# woodenHaptics_v_0_1.net
KiCad netlist of a schematic drawn in EAGLE
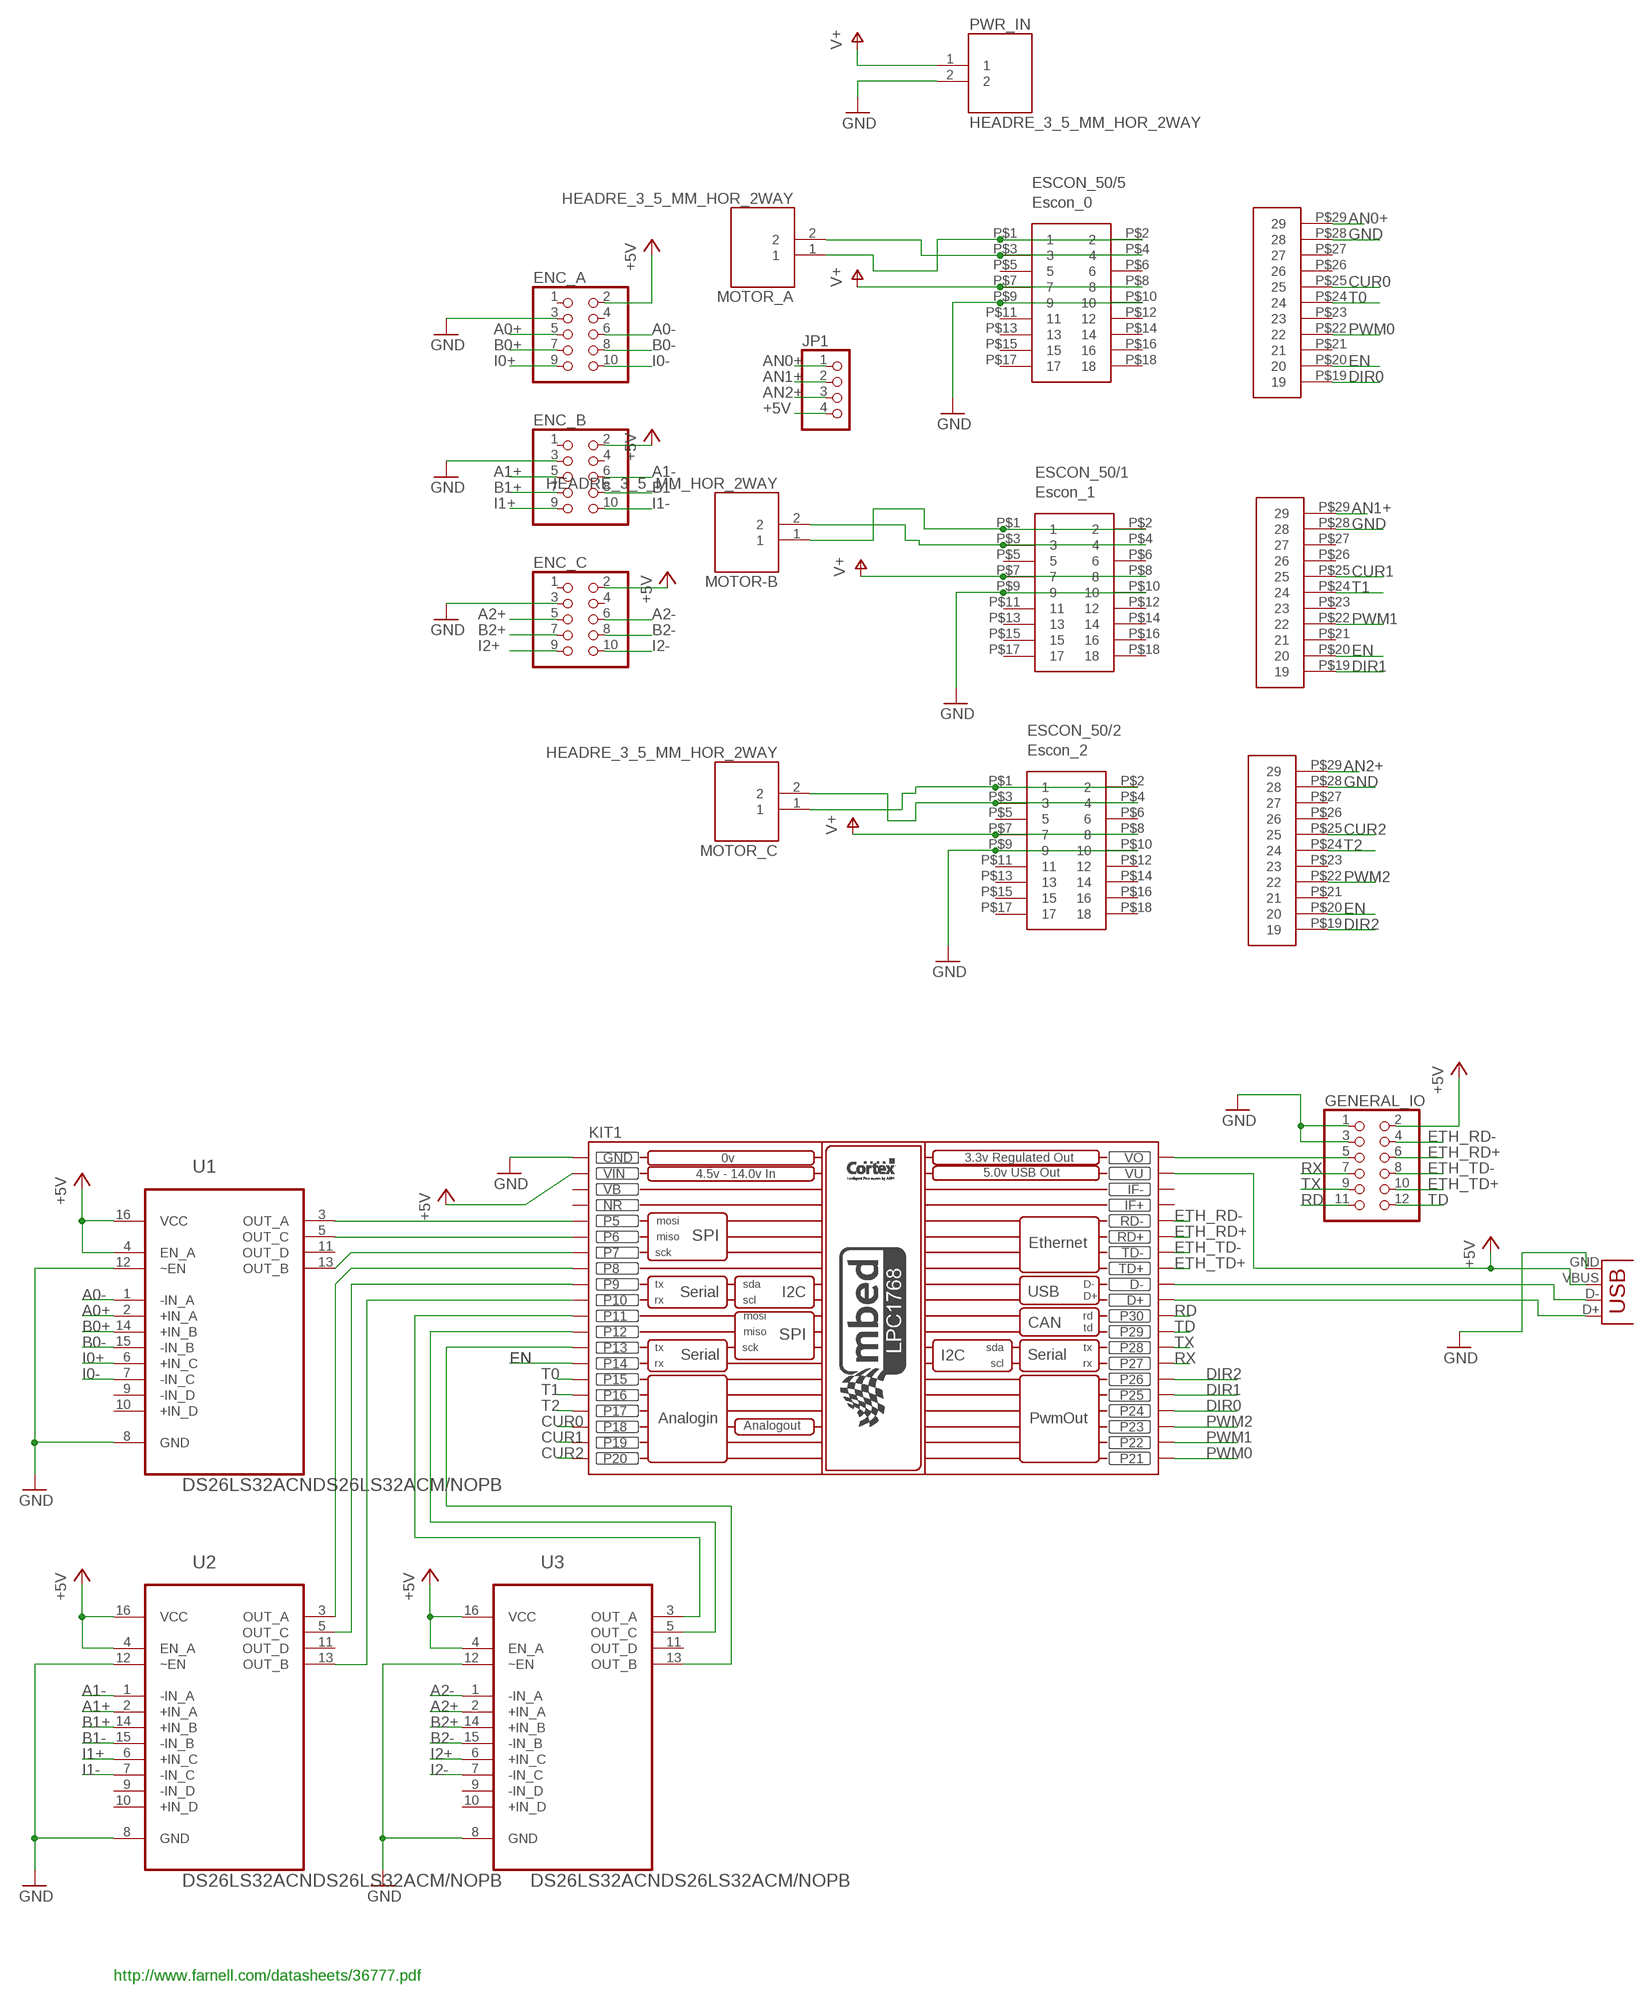
[diagram p0: schematic, sheet 1]

(export (version "E")
  (design (tool "Eeschema 10.0.6"))
  (components
    (comp (ref "ENC_A")
      (value "PINHD-2X5")
      (footprint "eagle-import:2X05")
      (libsource (lib "eagle-import") (part "PINHD-2X5"))
    )
    (comp (ref "ENC_B")
      (value "PINHD-2X5")
      (footprint "eagle-import:2X05")
      (libsource (lib "eagle-import") (part "PINHD-2X5"))
    )
    (comp (ref "ENC_C")
      (value "PINHD-2X5")
      (footprint "eagle-import:2X05")
      (libsource (lib "eagle-import") (part "PINHD-2X5"))
    )
    (comp (ref "ESCON_50/1")
      (value "Escon_1")
      (footprint "eagle-import:MODULE")
      (libsource (lib "eagle-import") (part "ESCON_MODULE_50/5"))
    )
    (comp (ref "ESCON_50/2")
      (value "Escon_2")
      (footprint "eagle-import:MODULE")
      (libsource (lib "eagle-import") (part "ESCON_MODULE_50/5"))
    )
    (comp (ref "ESCON_50/5")
      (value "Escon_0")
      (footprint "eagle-import:MODULE")
      (libsource (lib "eagle-import") (part "ESCON_MODULE_50/5"))
    )
    (comp (ref "GENERAL_IO")
      (value "PINHD-2X6")
      (footprint "eagle-import:2X06")
      (libsource (lib "eagle-import") (part "PINHD-2X6"))
    )
    (comp (ref "JP1")
      (value "PINHD-1X4")
      (footprint "eagle-import:1X04")
      (libsource (lib "eagle-import") (part "PINHD-1X4"))
    )
    (comp (ref "KIT1")
      (value "MBED_NXP_LPC1768")
      (footprint "eagle-import:MBED-KIT")
      (libsource (lib "eagle-import") (part "MBED_NXP_LPC1768"))
    )
    (comp (ref "MOTOR-B")
      (value "HEADRE_3_5_MM_HOR_2WAY")
      (footprint "eagle-import:HEADER_3_5MM_HOR_2WAY")
      (libsource (lib "eagle-import") (part "HEADRE_3_5_MM_HOR_2WAY"))
    )
    (comp (ref "MOTOR_A")
      (value "HEADRE_3_5_MM_HOR_2WAY")
      (footprint "eagle-import:HEADER_3_5MM_HOR_2WAY")
      (libsource (lib "eagle-import") (part "HEADRE_3_5_MM_HOR_2WAY"))
    )
    (comp (ref "MOTOR_C")
      (value "HEADRE_3_5_MM_HOR_2WAY")
      (footprint "eagle-import:HEADER_3_5MM_HOR_2WAY")
      (libsource (lib "eagle-import") (part "HEADRE_3_5_MM_HOR_2WAY"))
    )
    (comp (ref "PWR_IN")
      (value "HEADRE_3_5_MM_HOR_2WAY")
      (footprint "eagle-import:HEADER_3_5MM_HOR_2WAY")
      (libsource (lib "eagle-import") (part "HEADRE_3_5_MM_HOR_2WAY"))
    )
    (comp (ref "U1")
      (value "DS26LS32ACNDS26LS32ACM/NOPB")
      (footprint "eagle-import:M16")
      (libsource (lib "eagle-import") (part "DS26LS32ACNDS26LS32ACM/NOPB"))
    )
    (comp (ref "U2")
      (value "DS26LS32ACNDS26LS32ACM/NOPB")
      (footprint "eagle-import:M16")
      (libsource (lib "eagle-import") (part "DS26LS32ACNDS26LS32ACM/NOPB"))
    )
    (comp (ref "U3")
      (value "DS26LS32ACNDS26LS32ACM/NOPB")
      (footprint "eagle-import:M16")
      (libsource (lib "eagle-import") (part "DS26LS32ACNDS26LS32ACM/NOPB"))
    )
    (comp (ref "X2")
      (value "Micro USB")
      (footprint "eagle-import:USB-MICROB")
      (libsource (lib "eagle-import") (part "USB-MICROB"))
    )
  )
  (nets
    (net (code "1") (name "+5V") (class "Default")
      (node (ref "ENC_A") (pin "2") (pinfunction "2_2") (pintype "passive"))
      (node (ref "ENC_B") (pin "2") (pinfunction "2_2") (pintype "passive"))
      (node (ref "ENC_C") (pin "2") (pinfunction "2_2") (pintype "passive"))
      (node (ref "GENERAL_IO") (pin "2") (pinfunction "2_2") (pintype "passive"))
      (node (ref "JP1") (pin "4") (pinfunction "4_4") (pintype "passive"))
      (node (ref "KIT1") (pin "VIN") (pinfunction "VIN_VIN") (pintype "power_in"))
      (node (ref "KIT1") (pin "VU") (pinfunction "VU_VU") (pintype "power_in"))
      (node (ref "U1") (pin "16") (pinfunction "VCC_16") (pintype "power_in"))
      (node (ref "U1") (pin "4") (pinfunction "EN_A_4") (pintype "input"))
      (node (ref "U2") (pin "16") (pinfunction "VCC_16") (pintype "power_in"))
      (node (ref "U2") (pin "4") (pinfunction "EN_A_4") (pintype "input"))
      (node (ref "U3") (pin "16") (pinfunction "VCC_16") (pintype "power_in"))
      (node (ref "U3") (pin "4") (pinfunction "EN_A_4") (pintype "input"))
      (node (ref "X2") (pin "VBUS") (pinfunction "VBUS_VBUS") (pintype "bidirectional"))
    )
    (net (code "2") (name "/A0+") (class "Default")
      (node (ref "ENC_A") (pin "5") (pinfunction "5_5") (pintype "passive"))
      (node (ref "U1") (pin "2") (pinfunction "+IN_A_2") (pintype "input"))
    )
    (net (code "3") (name "/A0-") (class "Default")
      (node (ref "ENC_A") (pin "6") (pinfunction "6_6") (pintype "passive"))
      (node (ref "U1") (pin "1") (pinfunction "-IN_A_1") (pintype "input"))
    )
    (net (code "4") (name "/A1+") (class "Default")
      (node (ref "ENC_B") (pin "5") (pinfunction "5_5") (pintype "passive"))
      (node (ref "U2") (pin "2") (pinfunction "+IN_A_2") (pintype "input"))
    )
    (net (code "5") (name "/A1-") (class "Default")
      (node (ref "ENC_B") (pin "6") (pinfunction "6_6") (pintype "passive"))
      (node (ref "U2") (pin "1") (pinfunction "-IN_A_1") (pintype "input"))
    )
    (net (code "6") (name "/A2+") (class "Default")
      (node (ref "ENC_C") (pin "5") (pinfunction "5_5") (pintype "passive"))
      (node (ref "U3") (pin "2") (pinfunction "+IN_A_2") (pintype "input"))
    )
    (net (code "7") (name "/A2-") (class "Default")
      (node (ref "ENC_C") (pin "6") (pinfunction "6_6") (pintype "passive"))
      (node (ref "U3") (pin "1") (pinfunction "-IN_A_1") (pintype "input"))
    )
    (net (code "8") (name "/AN0+") (class "Default")
      (node (ref "ESCON_50/5") (pin "P$29") (pinfunction "29_P$29") (pintype "bidirectional"))
      (node (ref "JP1") (pin "1") (pinfunction "1_1") (pintype "passive"))
    )
    (net (code "9") (name "/AN1+") (class "Default")
      (node (ref "ESCON_50/1") (pin "P$29") (pinfunction "29_P$29") (pintype "bidirectional"))
      (node (ref "JP1") (pin "2") (pinfunction "2_2") (pintype "passive"))
    )
    (net (code "10") (name "/AN2+") (class "Default")
      (node (ref "ESCON_50/2") (pin "P$29") (pinfunction "29_P$29") (pintype "bidirectional"))
      (node (ref "JP1") (pin "3") (pinfunction "3_3") (pintype "passive"))
    )
    (net (code "11") (name "/B0+") (class "Default")
      (node (ref "ENC_A") (pin "7") (pinfunction "7_7") (pintype "passive"))
      (node (ref "U1") (pin "14") (pinfunction "+IN_B_14") (pintype "input"))
    )
    (net (code "12") (name "/B0-") (class "Default")
      (node (ref "ENC_A") (pin "8") (pinfunction "8_8") (pintype "passive"))
      (node (ref "U1") (pin "15") (pinfunction "-IN_B_15") (pintype "input"))
    )
    (net (code "13") (name "/B1+") (class "Default")
      (node (ref "ENC_B") (pin "7") (pinfunction "7_7") (pintype "passive"))
      (node (ref "U2") (pin "14") (pinfunction "+IN_B_14") (pintype "input"))
    )
    (net (code "14") (name "/B1-") (class "Default")
      (node (ref "ENC_B") (pin "8") (pinfunction "8_8") (pintype "passive"))
      (node (ref "U2") (pin "15") (pinfunction "-IN_B_15") (pintype "input"))
    )
    (net (code "15") (name "/B2+") (class "Default")
      (node (ref "ENC_C") (pin "7") (pinfunction "7_7") (pintype "passive"))
      (node (ref "U3") (pin "14") (pinfunction "+IN_B_14") (pintype "input"))
    )
    (net (code "16") (name "/B2-") (class "Default")
      (node (ref "ENC_C") (pin "8") (pinfunction "8_8") (pintype "passive"))
      (node (ref "U3") (pin "15") (pinfunction "-IN_B_15") (pintype "input"))
    )
    (net (code "17") (name "/CUR0") (class "Default")
      (node (ref "ESCON_50/5") (pin "P$25") (pinfunction "25_P$25") (pintype "bidirectional"))
      (node (ref "KIT1") (pin "P$18") (pinfunction "P18_P$18") (pintype "bidirectional"))
    )
    (net (code "18") (name "/CUR1") (class "Default")
      (node (ref "ESCON_50/1") (pin "P$25") (pinfunction "25_P$25") (pintype "bidirectional"))
      (node (ref "KIT1") (pin "P$19") (pinfunction "P19_P$19") (pintype "bidirectional"))
    )
    (net (code "19") (name "/CUR2") (class "Default")
      (node (ref "ESCON_50/2") (pin "P$25") (pinfunction "25_P$25") (pintype "bidirectional"))
      (node (ref "KIT1") (pin "P$20") (pinfunction "P20_P$20") (pintype "bidirectional"))
    )
    (net (code "20") (name "/DIR0") (class "Default")
      (node (ref "ESCON_50/5") (pin "P$19") (pinfunction "19_P$19") (pintype "bidirectional"))
      (node (ref "KIT1") (pin "P$24") (pinfunction "P24_P$24") (pintype "bidirectional"))
    )
    (net (code "21") (name "/DIR1") (class "Default")
      (node (ref "ESCON_50/1") (pin "P$19") (pinfunction "19_P$19") (pintype "bidirectional"))
      (node (ref "KIT1") (pin "P$25") (pinfunction "P25_P$25") (pintype "bidirectional"))
    )
    (net (code "22") (name "/DIR2") (class "Default")
      (node (ref "ESCON_50/2") (pin "P$19") (pinfunction "19_P$19") (pintype "bidirectional"))
      (node (ref "KIT1") (pin "P$26") (pinfunction "P26_P$26") (pintype "bidirectional"))
    )
    (net (code "23") (name "/EN") (class "Default")
      (node (ref "ESCON_50/1") (pin "P$20") (pinfunction "20_P$20") (pintype "bidirectional"))
      (node (ref "ESCON_50/2") (pin "P$20") (pinfunction "20_P$20") (pintype "bidirectional"))
      (node (ref "ESCON_50/5") (pin "P$20") (pinfunction "20_P$20") (pintype "bidirectional"))
      (node (ref "KIT1") (pin "P$14") (pinfunction "P14_P$14") (pintype "bidirectional"))
    )
    (net (code "24") (name "/ETH_RD+") (class "Default")
      (node (ref "GENERAL_IO") (pin "6") (pinfunction "6_6") (pintype "passive"))
      (node (ref "KIT1") (pin "RD+") (pinfunction "RD+_RD+") (pintype "bidirectional"))
    )
    (net (code "25") (name "/ETH_RD-") (class "Default")
      (node (ref "GENERAL_IO") (pin "4") (pinfunction "4_4") (pintype "passive"))
      (node (ref "KIT1") (pin "RD-") (pinfunction "RD-_RD-") (pintype "bidirectional"))
    )
    (net (code "26") (name "/ETH_TD+") (class "Default")
      (node (ref "GENERAL_IO") (pin "10") (pinfunction "10_10") (pintype "passive"))
      (node (ref "KIT1") (pin "TD+") (pinfunction "TD+_TD+") (pintype "bidirectional"))
    )
    (net (code "27") (name "/ETH_TD-") (class "Default")
      (node (ref "GENERAL_IO") (pin "8") (pinfunction "8_8") (pintype "passive"))
      (node (ref "KIT1") (pin "TD-") (pinfunction "TD-_TD-") (pintype "bidirectional"))
    )
    (net (code "28") (name "/I0+") (class "Default")
      (node (ref "ENC_A") (pin "9") (pinfunction "9_9") (pintype "passive"))
      (node (ref "U1") (pin "6") (pinfunction "+IN_C_6") (pintype "input"))
    )
    (net (code "29") (name "/I0-") (class "Default")
      (node (ref "ENC_A") (pin "10") (pinfunction "10_10") (pintype "passive"))
      (node (ref "U1") (pin "7") (pinfunction "-IN_C_7") (pintype "input"))
    )
    (net (code "30") (name "/I1+") (class "Default")
      (node (ref "ENC_B") (pin "9") (pinfunction "9_9") (pintype "passive"))
      (node (ref "U2") (pin "6") (pinfunction "+IN_C_6") (pintype "input"))
    )
    (net (code "31") (name "/I1-") (class "Default")
      (node (ref "ENC_B") (pin "10") (pinfunction "10_10") (pintype "passive"))
      (node (ref "U2") (pin "7") (pinfunction "-IN_C_7") (pintype "input"))
    )
    (net (code "32") (name "/I2+") (class "Default")
      (node (ref "ENC_C") (pin "9") (pinfunction "9_9") (pintype "passive"))
      (node (ref "U3") (pin "6") (pinfunction "+IN_C_6") (pintype "input"))
    )
    (net (code "33") (name "/I2-") (class "Default")
      (node (ref "ENC_C") (pin "10") (pinfunction "10_10") (pintype "passive"))
      (node (ref "U3") (pin "7") (pinfunction "-IN_C_7") (pintype "input"))
    )
    (net (code "34") (name "/NR") (class "Default")
      (node (ref "KIT1") (pin "NR") (pinfunction "NR_NR") (pintype "power_in"))
    )
    (net (code "35") (name "/PWM0") (class "Default")
      (node (ref "ESCON_50/5") (pin "P$22") (pinfunction "22_P$22") (pintype "bidirectional"))
      (node (ref "KIT1") (pin "P$21") (pinfunction "P21_P$21") (pintype "bidirectional"))
    )
    (net (code "36") (name "/PWM1") (class "Default")
      (node (ref "ESCON_50/1") (pin "P$22") (pinfunction "22_P$22") (pintype "bidirectional"))
      (node (ref "KIT1") (pin "P$22") (pinfunction "P22_P$22") (pintype "bidirectional"))
    )
    (net (code "37") (name "/PWM2") (class "Default")
      (node (ref "ESCON_50/2") (pin "P$22") (pinfunction "22_P$22") (pintype "bidirectional"))
      (node (ref "KIT1") (pin "P$23") (pinfunction "P23_P$23") (pintype "bidirectional"))
    )
    (net (code "38") (name "/RD") (class "Default")
      (node (ref "GENERAL_IO") (pin "11") (pinfunction "11_11") (pintype "passive"))
      (node (ref "KIT1") (pin "P$30") (pinfunction "P30_P$30") (pintype "bidirectional"))
    )
    (net (code "39") (name "/RX") (class "Default")
      (node (ref "GENERAL_IO") (pin "7") (pinfunction "7_7") (pintype "passive"))
      (node (ref "KIT1") (pin "P$27") (pinfunction "P27_P$27") (pintype "bidirectional"))
    )
    (net (code "40") (name "/T0") (class "Default")
      (node (ref "ESCON_50/5") (pin "P$24") (pinfunction "24_P$24") (pintype "bidirectional"))
      (node (ref "KIT1") (pin "P$15") (pinfunction "P15_P$15") (pintype "bidirectional"))
    )
    (net (code "41") (name "/T1") (class "Default")
      (node (ref "ESCON_50/1") (pin "P$24") (pinfunction "24_P$24") (pintype "bidirectional"))
      (node (ref "KIT1") (pin "P$16") (pinfunction "P16_P$16") (pintype "bidirectional"))
    )
    (net (code "42") (name "/T2") (class "Default")
      (node (ref "ESCON_50/2") (pin "P$24") (pinfunction "24_P$24") (pintype "bidirectional"))
      (node (ref "KIT1") (pin "P$17") (pinfunction "P17_P$17") (pintype "bidirectional"))
    )
    (net (code "43") (name "/TD") (class "Default")
      (node (ref "GENERAL_IO") (pin "12") (pinfunction "12_12") (pintype "passive"))
      (node (ref "KIT1") (pin "P$29") (pinfunction "P29_P$29") (pintype "bidirectional"))
    )
    (net (code "44") (name "/TX") (class "Default")
      (node (ref "GENERAL_IO") (pin "9") (pinfunction "9_9") (pintype "passive"))
      (node (ref "KIT1") (pin "P$28") (pinfunction "P28_P$28") (pintype "bidirectional"))
    )
    (net (code "45") (name "/VB") (class "Default")
      (node (ref "KIT1") (pin "VB") (pinfunction "VB_VB") (pintype "power_in"))
    )
    (net (code "46") (name "GND") (class "Default")
      (node (ref "ENC_A") (pin "3") (pinfunction "3_3") (pintype "passive"))
      (node (ref "ENC_B") (pin "3") (pinfunction "3_3") (pintype "passive"))
      (node (ref "ENC_C") (pin "3") (pinfunction "3_3") (pintype "passive"))
      (node (ref "ESCON_50/1") (pin "P$10") (pinfunction "10_P$10") (pintype "power_in"))
      (node (ref "ESCON_50/1") (pin "P$28") (pinfunction "28_P$28") (pintype "bidirectional"))
      (node (ref "ESCON_50/1") (pin "P$9") (pinfunction "9_P$9") (pintype "power_in"))
      (node (ref "ESCON_50/2") (pin "P$10") (pinfunction "10_P$10") (pintype "power_in"))
      (node (ref "ESCON_50/2") (pin "P$28") (pinfunction "28_P$28") (pintype "bidirectional"))
      (node (ref "ESCON_50/2") (pin "P$9") (pinfunction "9_P$9") (pintype "power_in"))
      (node (ref "ESCON_50/5") (pin "P$10") (pinfunction "10_P$10") (pintype "power_in"))
      (node (ref "ESCON_50/5") (pin "P$28") (pinfunction "28_P$28") (pintype "bidirectional"))
      (node (ref "ESCON_50/5") (pin "P$9") (pinfunction "9_P$9") (pintype "power_in"))
      (node (ref "GENERAL_IO") (pin "1") (pinfunction "1_1") (pintype "passive"))
      (node (ref "GENERAL_IO") (pin "3") (pinfunction "3_3") (pintype "passive"))
      (node (ref "KIT1") (pin "GND") (pinfunction "GND_GND") (pintype "power_in"))
      (node (ref "PWR_IN") (pin "2") (pinfunction "2_2") (pintype "bidirectional"))
      (node (ref "U1") (pin "12") (pinfunction "~{EN}_12") (pintype "input"))
      (node (ref "U1") (pin "8") (pinfunction "GND_8") (pintype "passive"))
      (node (ref "U2") (pin "12") (pinfunction "~{EN}_12") (pintype "input"))
      (node (ref "U2") (pin "8") (pinfunction "GND_8") (pintype "passive"))
      (node (ref "U3") (pin "12") (pinfunction "~{EN}_12") (pintype "input"))
      (node (ref "U3") (pin "8") (pinfunction "GND_8") (pintype "passive"))
      (node (ref "X2") (pin "GND") (pinfunction "GND_GND") (pintype "bidirectional"))
    )
    (net (code "47") (name "Net-(ESCON_50/1-1)") (class "Default")
      (node (ref "ESCON_50/1") (pin "P$1") (pinfunction "1_P$1") (pintype "bidirectional"))
      (node (ref "ESCON_50/1") (pin "P$2") (pinfunction "2_P$2") (pintype "bidirectional"))
      (node (ref "MOTOR-B") (pin "1") (pinfunction "1_1") (pintype "bidirectional"))
    )
    (net (code "48") (name "Net-(ESCON_50/1-3)") (class "Default")
      (node (ref "ESCON_50/1") (pin "P$3") (pinfunction "3_P$3") (pintype "bidirectional"))
      (node (ref "ESCON_50/1") (pin "P$4") (pinfunction "4_P$4") (pintype "bidirectional"))
      (node (ref "MOTOR-B") (pin "2") (pinfunction "2_2") (pintype "bidirectional"))
    )
    (net (code "49") (name "Net-(ESCON_50/2-1)") (class "Default")
      (node (ref "ESCON_50/2") (pin "P$1") (pinfunction "1_P$1") (pintype "bidirectional"))
      (node (ref "ESCON_50/2") (pin "P$2") (pinfunction "2_P$2") (pintype "bidirectional"))
      (node (ref "MOTOR_C") (pin "1") (pinfunction "1_1") (pintype "bidirectional"))
    )
    (net (code "50") (name "Net-(ESCON_50/2-3)") (class "Default")
      (node (ref "ESCON_50/2") (pin "P$3") (pinfunction "3_P$3") (pintype "bidirectional"))
      (node (ref "ESCON_50/2") (pin "P$4") (pinfunction "4_P$4") (pintype "bidirectional"))
      (node (ref "MOTOR_C") (pin "2") (pinfunction "2_2") (pintype "bidirectional"))
    )
    (net (code "51") (name "Net-(ESCON_50/5-1)") (class "Default")
      (node (ref "ESCON_50/5") (pin "P$1") (pinfunction "1_P$1") (pintype "bidirectional"))
      (node (ref "ESCON_50/5") (pin "P$2") (pinfunction "2_P$2") (pintype "bidirectional"))
      (node (ref "MOTOR_A") (pin "1") (pinfunction "1_1") (pintype "bidirectional"))
    )
    (net (code "52") (name "Net-(ESCON_50/5-3)") (class "Default")
      (node (ref "ESCON_50/5") (pin "P$3") (pinfunction "3_P$3") (pintype "bidirectional"))
      (node (ref "ESCON_50/5") (pin "P$4") (pinfunction "4_P$4") (pintype "bidirectional"))
      (node (ref "MOTOR_A") (pin "2") (pinfunction "2_2") (pintype "bidirectional"))
    )
    (net (code "53") (name "Net-(KIT1-P5)") (class "Default")
      (node (ref "KIT1") (pin "P$5") (pinfunction "P5_P$5") (pintype "bidirectional"))
      (node (ref "U1") (pin "3") (pinfunction "OUT_A_3") (pintype "output"))
    )
    (net (code "54") (name "Net-(KIT1-P6)") (class "Default")
      (node (ref "KIT1") (pin "P$6") (pinfunction "P6_P$6") (pintype "bidirectional"))
      (node (ref "U1") (pin "5") (pinfunction "OUT_C_5") (pintype "output"))
    )
    (net (code "55") (name "Net-(KIT1-P7)") (class "Default")
      (node (ref "KIT1") (pin "P$7") (pinfunction "P7_P$7") (pintype "bidirectional"))
      (node (ref "U1") (pin "13") (pinfunction "OUT_B_13") (pintype "output"))
    )
    (net (code "56") (name "Net-(KIT1-P8)") (class "Default")
      (node (ref "KIT1") (pin "P$8") (pinfunction "P8_P$8") (pintype "bidirectional"))
      (node (ref "U2") (pin "3") (pinfunction "OUT_A_3") (pintype "output"))
    )
    (net (code "57") (name "Net-(KIT1-P9)") (class "Default")
      (node (ref "KIT1") (pin "P$9") (pinfunction "P9_P$9") (pintype "bidirectional"))
      (node (ref "U2") (pin "5") (pinfunction "OUT_C_5") (pintype "output"))
    )
    (net (code "58") (name "Net-(KIT1-P10)") (class "Default")
      (node (ref "KIT1") (pin "P$10") (pinfunction "P10_P$10") (pintype "bidirectional"))
      (node (ref "U2") (pin "13") (pinfunction "OUT_B_13") (pintype "output"))
    )
    (net (code "59") (name "Net-(KIT1-P11)") (class "Default")
      (node (ref "KIT1") (pin "P$11") (pinfunction "P11_P$11") (pintype "bidirectional"))
      (node (ref "U3") (pin "3") (pinfunction "OUT_A_3") (pintype "output"))
    )
    (net (code "60") (name "Net-(KIT1-P12)") (class "Default")
      (node (ref "KIT1") (pin "P$12") (pinfunction "P12_P$12") (pintype "bidirectional"))
      (node (ref "U3") (pin "5") (pinfunction "OUT_C_5") (pintype "output"))
    )
    (net (code "61") (name "Net-(KIT1-P13)") (class "Default")
      (node (ref "KIT1") (pin "P$13") (pinfunction "P13_P$13") (pintype "bidirectional"))
      (node (ref "U3") (pin "13") (pinfunction "OUT_B_13") (pintype "output"))
    )
    (net (code "62") (name "Net-(KIT1-PadD+)") (class "Default")
      (node (ref "KIT1") (pin "D+") (pinfunction "D+_D+") (pintype "bidirectional"))
      (node (ref "X2") (pin "D+") (pinfunction "D+_D+") (pintype "bidirectional"))
    )
    (net (code "63") (name "Net-(KIT1-PadD-)") (class "Default")
      (node (ref "KIT1") (pin "D-") (pinfunction "D-_D-") (pintype "bidirectional"))
      (node (ref "X2") (pin "D-") (pinfunction "D-_D-") (pintype "bidirectional"))
    )
    (net (code "64") (name "Net-(KIT1-VO)") (class "Default")
      (node (ref "GENERAL_IO") (pin "5") (pinfunction "5_5") (pintype "passive"))
      (node (ref "KIT1") (pin "VOUT") (pinfunction "VO_VOUT") (pintype "power_in"))
    )
    (net (code "65") (name "V+") (class "Default")
      (node (ref "ESCON_50/1") (pin "P$7") (pinfunction "7_P$7") (pintype "power_in"))
      (node (ref "ESCON_50/1") (pin "P$8") (pinfunction "8_P$8") (pintype "power_in"))
      (node (ref "ESCON_50/2") (pin "P$7") (pinfunction "7_P$7") (pintype "power_in"))
      (node (ref "ESCON_50/2") (pin "P$8") (pinfunction "8_P$8") (pintype "power_in"))
      (node (ref "ESCON_50/5") (pin "P$7") (pinfunction "7_P$7") (pintype "power_in"))
      (node (ref "ESCON_50/5") (pin "P$8") (pinfunction "8_P$8") (pintype "power_in"))
      (node (ref "PWR_IN") (pin "1") (pinfunction "1_1") (pintype "bidirectional"))
    )
    (net (code "66") (name "unconnected-(ENC_A-Pad1)") (class "Default")
      (node (ref "ENC_A") (pin "1") (pinfunction "1_1") (pintype "passive"))
    )
    (net (code "67") (name "unconnected-(ENC_A-Pad4)") (class "Default")
      (node (ref "ENC_A") (pin "4") (pinfunction "4_4") (pintype "passive"))
    )
    (net (code "68") (name "unconnected-(ENC_B-Pad1)") (class "Default")
      (node (ref "ENC_B") (pin "1") (pinfunction "1_1") (pintype "passive"))
    )
    (net (code "69") (name "unconnected-(ENC_B-Pad4)") (class "Default")
      (node (ref "ENC_B") (pin "4") (pinfunction "4_4") (pintype "passive"))
    )
    (net (code "70") (name "unconnected-(ENC_C-Pad1)") (class "Default")
      (node (ref "ENC_C") (pin "1") (pinfunction "1_1") (pintype "passive"))
    )
    (net (code "71") (name "unconnected-(ENC_C-Pad4)") (class "Default")
      (node (ref "ENC_C") (pin "4") (pinfunction "4_4") (pintype "passive"))
    )
    (net (code "72") (name "unconnected-(ESCON_50/1-5-PadP$5)") (class "Default")
      (node (ref "ESCON_50/1") (pin "P$5") (pinfunction "5_P$5") (pintype "bidirectional"))
    )
    (net (code "73") (name "unconnected-(ESCON_50/1-6-PadP$6)") (class "Default")
      (node (ref "ESCON_50/1") (pin "P$6") (pinfunction "6_P$6") (pintype "bidirectional"))
    )
    (net (code "74") (name "unconnected-(ESCON_50/1-11-PadP$11)") (class "Default")
      (node (ref "ESCON_50/1") (pin "P$11") (pinfunction "11_P$11") (pintype "bidirectional"))
    )
    (net (code "75") (name "unconnected-(ESCON_50/1-12-PadP$12)") (class "Default")
      (node (ref "ESCON_50/1") (pin "P$12") (pinfunction "12_P$12") (pintype "bidirectional"))
    )
    (net (code "76") (name "unconnected-(ESCON_50/1-13-PadP$13)") (class "Default")
      (node (ref "ESCON_50/1") (pin "P$13") (pinfunction "13_P$13") (pintype "bidirectional"))
    )
    (net (code "77") (name "unconnected-(ESCON_50/1-14-PadP$14)") (class "Default")
      (node (ref "ESCON_50/1") (pin "P$14") (pinfunction "14_P$14") (pintype "bidirectional"))
    )
    (net (code "78") (name "unconnected-(ESCON_50/1-15-PadP$15)") (class "Default")
      (node (ref "ESCON_50/1") (pin "P$15") (pinfunction "15_P$15") (pintype "bidirectional"))
    )
    (net (code "79") (name "unconnected-(ESCON_50/1-16-PadP$16)") (class "Default")
      (node (ref "ESCON_50/1") (pin "P$16") (pinfunction "16_P$16") (pintype "bidirectional"))
    )
    (net (code "80") (name "unconnected-(ESCON_50/1-17-PadP$17)") (class "Default")
      (node (ref "ESCON_50/1") (pin "P$17") (pinfunction "17_P$17") (pintype "bidirectional"))
    )
    (net (code "81") (name "unconnected-(ESCON_50/1-18-PadP$18)") (class "Default")
      (node (ref "ESCON_50/1") (pin "P$18") (pinfunction "18_P$18") (pintype "bidirectional"))
    )
    (net (code "82") (name "unconnected-(ESCON_50/1-21-PadP$21)") (class "Default")
      (node (ref "ESCON_50/1") (pin "P$21") (pinfunction "21_P$21") (pintype "bidirectional"))
    )
    (net (code "83") (name "unconnected-(ESCON_50/1-23-PadP$23)") (class "Default")
      (node (ref "ESCON_50/1") (pin "P$23") (pinfunction "23_P$23") (pintype "bidirectional"))
    )
    (net (code "84") (name "unconnected-(ESCON_50/1-26-PadP$26)") (class "Default")
      (node (ref "ESCON_50/1") (pin "P$26") (pinfunction "26_P$26") (pintype "bidirectional"))
    )
    (net (code "85") (name "unconnected-(ESCON_50/1-27-PadP$27)") (class "Default")
      (node (ref "ESCON_50/1") (pin "P$27") (pinfunction "27_P$27") (pintype "bidirectional"))
    )
    (net (code "86") (name "unconnected-(ESCON_50/2-5-PadP$5)") (class "Default")
      (node (ref "ESCON_50/2") (pin "P$5") (pinfunction "5_P$5") (pintype "bidirectional"))
    )
    (net (code "87") (name "unconnected-(ESCON_50/2-6-PadP$6)") (class "Default")
      (node (ref "ESCON_50/2") (pin "P$6") (pinfunction "6_P$6") (pintype "bidirectional"))
    )
    (net (code "88") (name "unconnected-(ESCON_50/2-11-PadP$11)") (class "Default")
      (node (ref "ESCON_50/2") (pin "P$11") (pinfunction "11_P$11") (pintype "bidirectional"))
    )
    (net (code "89") (name "unconnected-(ESCON_50/2-12-PadP$12)") (class "Default")
      (node (ref "ESCON_50/2") (pin "P$12") (pinfunction "12_P$12") (pintype "bidirectional"))
    )
    (net (code "90") (name "unconnected-(ESCON_50/2-13-PadP$13)") (class "Default")
      (node (ref "ESCON_50/2") (pin "P$13") (pinfunction "13_P$13") (pintype "bidirectional"))
    )
    (net (code "91") (name "unconnected-(ESCON_50/2-14-PadP$14)") (class "Default")
      (node (ref "ESCON_50/2") (pin "P$14") (pinfunction "14_P$14") (pintype "bidirectional"))
    )
    (net (code "92") (name "unconnected-(ESCON_50/2-15-PadP$15)") (class "Default")
      (node (ref "ESCON_50/2") (pin "P$15") (pinfunction "15_P$15") (pintype "bidirectional"))
    )
    (net (code "93") (name "unconnected-(ESCON_50/2-16-PadP$16)") (class "Default")
      (node (ref "ESCON_50/2") (pin "P$16") (pinfunction "16_P$16") (pintype "bidirectional"))
    )
    (net (code "94") (name "unconnected-(ESCON_50/2-17-PadP$17)") (class "Default")
      (node (ref "ESCON_50/2") (pin "P$17") (pinfunction "17_P$17") (pintype "bidirectional"))
    )
    (net (code "95") (name "unconnected-(ESCON_50/2-18-PadP$18)") (class "Default")
      (node (ref "ESCON_50/2") (pin "P$18") (pinfunction "18_P$18") (pintype "bidirectional"))
    )
    (net (code "96") (name "unconnected-(ESCON_50/2-21-PadP$21)") (class "Default")
      (node (ref "ESCON_50/2") (pin "P$21") (pinfunction "21_P$21") (pintype "bidirectional"))
    )
    (net (code "97") (name "unconnected-(ESCON_50/2-23-PadP$23)") (class "Default")
      (node (ref "ESCON_50/2") (pin "P$23") (pinfunction "23_P$23") (pintype "bidirectional"))
    )
    (net (code "98") (name "unconnected-(ESCON_50/2-26-PadP$26)") (class "Default")
      (node (ref "ESCON_50/2") (pin "P$26") (pinfunction "26_P$26") (pintype "bidirectional"))
    )
    (net (code "99") (name "unconnected-(ESCON_50/2-27-PadP$27)") (class "Default")
      (node (ref "ESCON_50/2") (pin "P$27") (pinfunction "27_P$27") (pintype "bidirectional"))
    )
    (net (code "100") (name "unconnected-(ESCON_50/5-5-PadP$5)") (class "Default")
      (node (ref "ESCON_50/5") (pin "P$5") (pinfunction "5_P$5") (pintype "bidirectional"))
    )
    (net (code "101") (name "unconnected-(ESCON_50/5-6-PadP$6)") (class "Default")
      (node (ref "ESCON_50/5") (pin "P$6") (pinfunction "6_P$6") (pintype "bidirectional"))
    )
    (net (code "102") (name "unconnected-(ESCON_50/5-11-PadP$11)") (class "Default")
      (node (ref "ESCON_50/5") (pin "P$11") (pinfunction "11_P$11") (pintype "bidirectional"))
    )
    (net (code "103") (name "unconnected-(ESCON_50/5-12-PadP$12)") (class "Default")
      (node (ref "ESCON_50/5") (pin "P$12") (pinfunction "12_P$12") (pintype "bidirectional"))
    )
    (net (code "104") (name "unconnected-(ESCON_50/5-13-PadP$13)") (class "Default")
      (node (ref "ESCON_50/5") (pin "P$13") (pinfunction "13_P$13") (pintype "bidirectional"))
    )
    (net (code "105") (name "unconnected-(ESCON_50/5-14-PadP$14)") (class "Default")
      (node (ref "ESCON_50/5") (pin "P$14") (pinfunction "14_P$14") (pintype "bidirectional"))
    )
    (net (code "106") (name "unconnected-(ESCON_50/5-15-PadP$15)") (class "Default")
      (node (ref "ESCON_50/5") (pin "P$15") (pinfunction "15_P$15") (pintype "bidirectional"))
    )
    (net (code "107") (name "unconnected-(ESCON_50/5-16-PadP$16)") (class "Default")
      (node (ref "ESCON_50/5") (pin "P$16") (pinfunction "16_P$16") (pintype "bidirectional"))
    )
    (net (code "108") (name "unconnected-(ESCON_50/5-17-PadP$17)") (class "Default")
      (node (ref "ESCON_50/5") (pin "P$17") (pinfunction "17_P$17") (pintype "bidirectional"))
    )
    (net (code "109") (name "unconnected-(ESCON_50/5-18-PadP$18)") (class "Default")
      (node (ref "ESCON_50/5") (pin "P$18") (pinfunction "18_P$18") (pintype "bidirectional"))
    )
    (net (code "110") (name "unconnected-(ESCON_50/5-21-PadP$21)") (class "Default")
      (node (ref "ESCON_50/5") (pin "P$21") (pinfunction "21_P$21") (pintype "bidirectional"))
    )
    (net (code "111") (name "unconnected-(ESCON_50/5-23-PadP$23)") (class "Default")
      (node (ref "ESCON_50/5") (pin "P$23") (pinfunction "23_P$23") (pintype "bidirectional"))
    )
    (net (code "112") (name "unconnected-(ESCON_50/5-26-PadP$26)") (class "Default")
      (node (ref "ESCON_50/5") (pin "P$26") (pinfunction "26_P$26") (pintype "bidirectional"))
    )
    (net (code "113") (name "unconnected-(ESCON_50/5-27-PadP$27)") (class "Default")
      (node (ref "ESCON_50/5") (pin "P$27") (pinfunction "27_P$27") (pintype "bidirectional"))
    )
    (net (code "114") (name "unconnected-(KIT1-PadIF+)") (class "Default")
      (node (ref "KIT1") (pin "IF+") (pinfunction "IF+_IF+") (pintype "bidirectional"))
    )
    (net (code "115") (name "unconnected-(KIT1-PadIF-)") (class "Default")
      (node (ref "KIT1") (pin "IF-") (pinfunction "IF-_IF-") (pintype "bidirectional"))
    )
    (net (code "116") (name "unconnected-(U1-+IN_D-Pad10)") (class "Default")
      (node (ref "U1") (pin "10") (pinfunction "+IN_D_10") (pintype "input"))
    )
    (net (code "117") (name "unconnected-(U1--IN_D-Pad9)") (class "Default")
      (node (ref "U1") (pin "9") (pinfunction "-IN_D_9") (pintype "input"))
    )
    (net (code "118") (name "unconnected-(U1-OUT_D-Pad11)") (class "Default")
      (node (ref "U1") (pin "11") (pinfunction "OUT_D_11") (pintype "output"))
    )
    (net (code "119") (name "unconnected-(U2-+IN_D-Pad10)") (class "Default")
      (node (ref "U2") (pin "10") (pinfunction "+IN_D_10") (pintype "input"))
    )
    (net (code "120") (name "unconnected-(U2--IN_D-Pad9)") (class "Default")
      (node (ref "U2") (pin "9") (pinfunction "-IN_D_9") (pintype "input"))
    )
    (net (code "121") (name "unconnected-(U2-OUT_D-Pad11)") (class "Default")
      (node (ref "U2") (pin "11") (pinfunction "OUT_D_11") (pintype "output"))
    )
    (net (code "122") (name "unconnected-(U3-+IN_D-Pad10)") (class "Default")
      (node (ref "U3") (pin "10") (pinfunction "+IN_D_10") (pintype "input"))
    )
    (net (code "123") (name "unconnected-(U3--IN_D-Pad9)") (class "Default")
      (node (ref "U3") (pin "9") (pinfunction "-IN_D_9") (pintype "input"))
    )
    (net (code "124") (name "unconnected-(U3-OUT_D-Pad11)") (class "Default")
      (node (ref "U3") (pin "11") (pinfunction "OUT_D_11") (pintype "output"))
    )
  )
)
